# FETbox_rev0_PCB.net
KiCad netlist of a schematic drawn in EAGLE
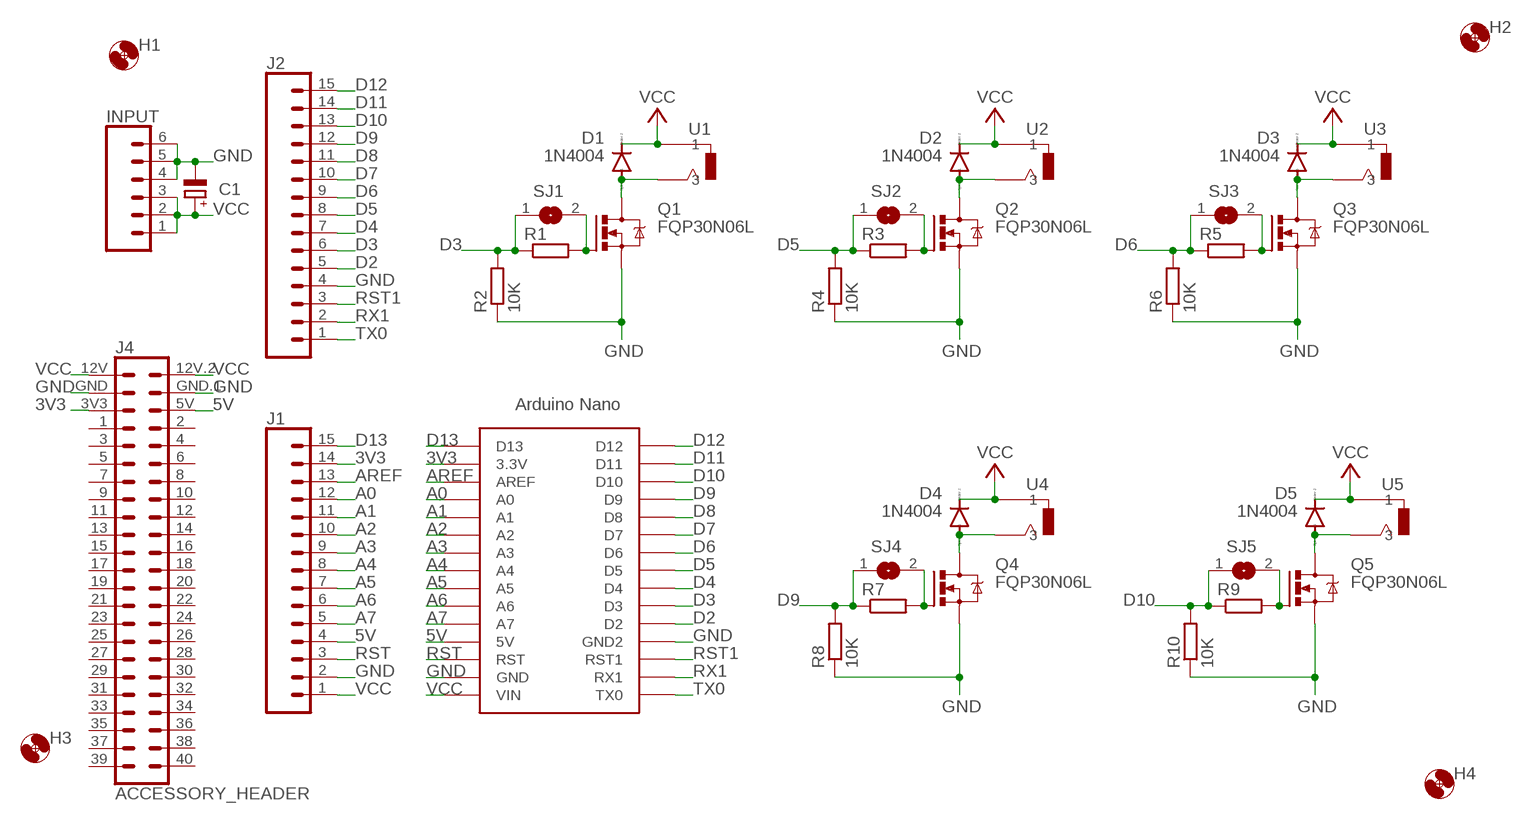
[diagram p0: schematic, sheet 1]

(export (version "E")
  (design (tool "Eeschema 10.0.6"))
  (components
    (comp (ref "C1")
      (value "CPOL-EUE2.5-6")
      (footprint "eagle-import:E2,5-6")
      (libsource (lib "eagle-import") (part "CPOL-EUE2.5-6"))
    )
    (comp (ref "D1")
      (value "1N4004")
      (footprint "eagle-import:DO41-10")
      (libsource (lib "eagle-import") (part "1N4004"))
    )
    (comp (ref "D2")
      (value "1N4004")
      (footprint "eagle-import:DO41-10")
      (libsource (lib "eagle-import") (part "1N4004"))
    )
    (comp (ref "D3")
      (value "1N4004")
      (footprint "eagle-import:DO41-10")
      (libsource (lib "eagle-import") (part "1N4004"))
    )
    (comp (ref "D4")
      (value "1N4004")
      (footprint "eagle-import:DO41-10")
      (libsource (lib "eagle-import") (part "1N4004"))
    )
    (comp (ref "D5")
      (value "1N4004")
      (footprint "eagle-import:DO41-10")
      (libsource (lib "eagle-import") (part "1N4004"))
    )
    (comp (ref "H1")
      (value "MOUNT-HOLE3.0")
      (footprint "eagle-import:3,0")
      (libsource (lib "eagle-import") (part "MOUNT-HOLE3.0"))
    )
    (comp (ref "H2")
      (value "MOUNT-HOLE3.0")
      (footprint "eagle-import:3,0")
      (libsource (lib "eagle-import") (part "MOUNT-HOLE3.0"))
    )
    (comp (ref "H3")
      (value "MOUNT-HOLE3.0")
      (footprint "eagle-import:3,0")
      (libsource (lib "eagle-import") (part "MOUNT-HOLE3.0"))
    )
    (comp (ref "H4")
      (value "MOUNT-HOLE3.0")
      (footprint "eagle-import:3,0")
      (libsource (lib "eagle-import") (part "MOUNT-HOLE3.0"))
    )
    (comp (ref "INPUT")
      (value "CONN_06LONGPADS")
      (footprint "eagle-import:1X06_LONGPADS")
      (libsource (lib "eagle-import") (part "CONN_06LONGPADS"))
    )
    (comp (ref "J1")
      (value "CONN_15")
      (footprint "eagle-import:1X15")
      (libsource (lib "eagle-import") (part "CONN_15"))
    )
    (comp (ref "J2")
      (value "CONN_15")
      (footprint "eagle-import:1X15")
      (libsource (lib "eagle-import") (part "CONN_15"))
    )
    (comp (ref "J4")
      (value "ACCESSORY_HEADER")
      (footprint "eagle-import:2X23")
      (libsource (lib "eagle-import") (part "ACCESSORY_HEADER"))
    )
    (comp (ref "Q1")
      (value "FQP30N06L")
      (footprint "eagle-import:TO220")
      (libsource (lib "eagle-import") (part "FQP30N06L"))
    )
    (comp (ref "Q2")
      (value "FQP30N06L")
      (footprint "eagle-import:TO220")
      (libsource (lib "eagle-import") (part "FQP30N06L"))
    )
    (comp (ref "Q3")
      (value "FQP30N06L")
      (footprint "eagle-import:TO220")
      (libsource (lib "eagle-import") (part "FQP30N06L"))
    )
    (comp (ref "Q4")
      (value "FQP30N06L")
      (footprint "eagle-import:TO220")
      (libsource (lib "eagle-import") (part "FQP30N06L"))
    )
    (comp (ref "Q5")
      (value "FQP30N06L")
      (footprint "eagle-import:TO220")
      (libsource (lib "eagle-import") (part "FQP30N06L"))
    )
    (comp (ref "R1")
      (value "100")
      (footprint "eagle-import:0207_10")
      (libsource (lib "eagle-import") (part "R-EU_0207/10"))
    )
    (comp (ref "R2")
      (value "10K")
      (footprint "eagle-import:0207_10")
      (libsource (lib "eagle-import") (part "R-EU_0207/10"))
    )
    (comp (ref "R3")
      (value "100")
      (footprint "eagle-import:0207_10")
      (libsource (lib "eagle-import") (part "R-EU_0207/10"))
    )
    (comp (ref "R4")
      (value "10K")
      (footprint "eagle-import:0207_10")
      (libsource (lib "eagle-import") (part "R-EU_0207/10"))
    )
    (comp (ref "R5")
      (value "100")
      (footprint "eagle-import:0207_10")
      (libsource (lib "eagle-import") (part "R-EU_0207/10"))
    )
    (comp (ref "R6")
      (value "10K")
      (footprint "eagle-import:0207_10")
      (libsource (lib "eagle-import") (part "R-EU_0207/10"))
    )
    (comp (ref "R7")
      (value "100")
      (footprint "eagle-import:0207_10")
      (libsource (lib "eagle-import") (part "R-EU_0207/10"))
    )
    (comp (ref "R8")
      (value "10K")
      (footprint "eagle-import:0207_10")
      (libsource (lib "eagle-import") (part "R-EU_0207/10"))
    )
    (comp (ref "R9")
      (value "100")
      (footprint "eagle-import:0207_10")
      (libsource (lib "eagle-import") (part "R-EU_0207/10"))
    )
    (comp (ref "R10")
      (value "10K")
      (footprint "eagle-import:0207_10")
      (libsource (lib "eagle-import") (part "R-EU_0207/10"))
    )
    (comp (ref "SJ1") (value "SJ") (footprint "eagle-import:SJ") (libsource (lib "eagle-import") (part "SJ")))
    (comp (ref "SJ2") (value "SJ") (footprint "eagle-import:SJ") (libsource (lib "eagle-import") (part "SJ")))
    (comp (ref "SJ3") (value "SJ") (footprint "eagle-import:SJ") (libsource (lib "eagle-import") (part "SJ")))
    (comp (ref "SJ4") (value "SJ") (footprint "eagle-import:SJ") (libsource (lib "eagle-import") (part "SJ")))
    (comp (ref "SJ5") (value "SJ") (footprint "eagle-import:SJ") (libsource (lib "eagle-import") (part "SJ")))
    (comp (ref "U$2")
      (value "NANO")
      (footprint "eagle-import:NANO")
      (libsource (lib "eagle-import") (part "NANO"))
    )
    (comp (ref "U1")
      (value "CL13845G")
      (footprint "eagle-import:CL13845G")
      (libsource (lib "eagle-import") (part "CL13845G"))
    )
    (comp (ref "U2")
      (value "CL13845G")
      (footprint "eagle-import:CL13845G")
      (libsource (lib "eagle-import") (part "CL13845G"))
    )
    (comp (ref "U3")
      (value "CL13845G")
      (footprint "eagle-import:CL13845G")
      (libsource (lib "eagle-import") (part "CL13845G"))
    )
    (comp (ref "U4")
      (value "CL13845G")
      (footprint "eagle-import:CL13845G")
      (libsource (lib "eagle-import") (part "CL13845G"))
    )
    (comp (ref "U5")
      (value "CL13845G")
      (footprint "eagle-import:CL13845G")
      (libsource (lib "eagle-import") (part "CL13845G"))
    )
  )
  (nets
    (net (code "1") (name "/3V3") (class "Default")
      (node (ref "J1") (pin "14") (pinfunction "14_14") (pintype "passive"))
      (node (ref "J4") (pin "3V3") (pinfunction "3V3_3V3") (pintype "passive"))
      (node (ref "U$2") (pin "3.3V") (pinfunction "3.3V_3.3V") (pintype "bidirectional"))
    )
    (net (code "2") (name "/5V") (class "Default")
      (node (ref "J1") (pin "4") (pinfunction "4_4") (pintype "passive"))
      (node (ref "J4") (pin "5V") (pinfunction "5V_5V") (pintype "passive"))
      (node (ref "U$2") (pin "5V") (pinfunction "5V_5V") (pintype "bidirectional"))
    )
    (net (code "3") (name "/A0") (class "Default")
      (node (ref "J1") (pin "12") (pinfunction "12_12") (pintype "passive"))
      (node (ref "U$2") (pin "A0") (pinfunction "A0_A0") (pintype "bidirectional"))
    )
    (net (code "4") (name "/A1") (class "Default")
      (node (ref "J1") (pin "11") (pinfunction "11_11") (pintype "passive"))
      (node (ref "U$2") (pin "A1") (pinfunction "A1_A1") (pintype "bidirectional"))
    )
    (net (code "5") (name "/A2") (class "Default")
      (node (ref "J1") (pin "10") (pinfunction "10_10") (pintype "passive"))
      (node (ref "U$2") (pin "A2") (pinfunction "A2_A2") (pintype "bidirectional"))
    )
    (net (code "6") (name "/A3") (class "Default")
      (node (ref "J1") (pin "9") (pinfunction "9_9") (pintype "passive"))
      (node (ref "U$2") (pin "A3") (pinfunction "A3_A3") (pintype "bidirectional"))
    )
    (net (code "7") (name "/A4") (class "Default")
      (node (ref "J1") (pin "8") (pinfunction "8_8") (pintype "passive"))
      (node (ref "U$2") (pin "A4") (pinfunction "A4_A4") (pintype "bidirectional"))
    )
    (net (code "8") (name "/A5") (class "Default")
      (node (ref "J1") (pin "7") (pinfunction "7_7") (pintype "passive"))
      (node (ref "U$2") (pin "A5") (pinfunction "A5_A5") (pintype "bidirectional"))
    )
    (net (code "9") (name "/A6") (class "Default")
      (node (ref "J1") (pin "6") (pinfunction "6_6") (pintype "passive"))
      (node (ref "U$2") (pin "A6") (pinfunction "A6_A6") (pintype "bidirectional"))
    )
    (net (code "10") (name "/A7") (class "Default")
      (node (ref "J1") (pin "5") (pinfunction "5_5") (pintype "passive"))
      (node (ref "U$2") (pin "A7") (pinfunction "A7_A7") (pintype "bidirectional"))
    )
    (net (code "11") (name "/AREF") (class "Default")
      (node (ref "J1") (pin "13") (pinfunction "13_13") (pintype "passive"))
      (node (ref "U$2") (pin "AREF") (pinfunction "AREF_AREF") (pintype "bidirectional"))
    )
    (net (code "12") (name "/D2") (class "Default")
      (node (ref "J2") (pin "5") (pinfunction "5_5") (pintype "passive"))
      (node (ref "U$2") (pin "D2") (pinfunction "D2_D2") (pintype "bidirectional"))
    )
    (net (code "13") (name "/D3") (class "Default")
      (node (ref "J2") (pin "6") (pinfunction "6_6") (pintype "passive"))
      (node (ref "R1") (pin "1") (pinfunction "1_1") (pintype "passive"))
      (node (ref "R2") (pin "2") (pinfunction "2_2") (pintype "passive"))
      (node (ref "SJ1") (pin "1") (pinfunction "1_1") (pintype "passive"))
      (node (ref "U$2") (pin "D3") (pinfunction "D3_D3") (pintype "bidirectional"))
    )
    (net (code "14") (name "/D4") (class "Default")
      (node (ref "J2") (pin "7") (pinfunction "7_7") (pintype "passive"))
      (node (ref "U$2") (pin "D4") (pinfunction "D4_D4") (pintype "bidirectional"))
    )
    (net (code "15") (name "/D5") (class "Default")
      (node (ref "J2") (pin "8") (pinfunction "8_8") (pintype "passive"))
      (node (ref "R3") (pin "1") (pinfunction "1_1") (pintype "passive"))
      (node (ref "R4") (pin "2") (pinfunction "2_2") (pintype "passive"))
      (node (ref "SJ2") (pin "1") (pinfunction "1_1") (pintype "passive"))
      (node (ref "U$2") (pin "D5") (pinfunction "D5_D5") (pintype "bidirectional"))
    )
    (net (code "16") (name "/D6") (class "Default")
      (node (ref "J2") (pin "9") (pinfunction "9_9") (pintype "passive"))
      (node (ref "R5") (pin "1") (pinfunction "1_1") (pintype "passive"))
      (node (ref "R6") (pin "2") (pinfunction "2_2") (pintype "passive"))
      (node (ref "SJ3") (pin "1") (pinfunction "1_1") (pintype "passive"))
      (node (ref "U$2") (pin "D6") (pinfunction "D6_D6") (pintype "bidirectional"))
    )
    (net (code "17") (name "/D7") (class "Default")
      (node (ref "J2") (pin "10") (pinfunction "10_10") (pintype "passive"))
      (node (ref "U$2") (pin "D7") (pinfunction "D7_D7") (pintype "bidirectional"))
    )
    (net (code "18") (name "/D8") (class "Default")
      (node (ref "J2") (pin "11") (pinfunction "11_11") (pintype "passive"))
      (node (ref "U$2") (pin "D8") (pinfunction "D8_D8") (pintype "bidirectional"))
    )
    (net (code "19") (name "/D9") (class "Default")
      (node (ref "J2") (pin "12") (pinfunction "12_12") (pintype "passive"))
      (node (ref "R7") (pin "1") (pinfunction "1_1") (pintype "passive"))
      (node (ref "R8") (pin "2") (pinfunction "2_2") (pintype "passive"))
      (node (ref "SJ4") (pin "1") (pinfunction "1_1") (pintype "passive"))
      (node (ref "U$2") (pin "D9") (pinfunction "D9_D9") (pintype "bidirectional"))
    )
    (net (code "20") (name "/D10") (class "Default")
      (node (ref "J2") (pin "13") (pinfunction "13_13") (pintype "passive"))
      (node (ref "R10") (pin "2") (pinfunction "2_2") (pintype "passive"))
      (node (ref "R9") (pin "1") (pinfunction "1_1") (pintype "passive"))
      (node (ref "SJ5") (pin "1") (pinfunction "1_1") (pintype "passive"))
      (node (ref "U$2") (pin "D10") (pinfunction "D10_D10") (pintype "bidirectional"))
    )
    (net (code "21") (name "/D11") (class "Default")
      (node (ref "J2") (pin "14") (pinfunction "14_14") (pintype "passive"))
      (node (ref "U$2") (pin "D11") (pinfunction "D11_D11") (pintype "bidirectional"))
    )
    (net (code "22") (name "/D12") (class "Default")
      (node (ref "J2") (pin "15") (pinfunction "15_15") (pintype "passive"))
      (node (ref "U$2") (pin "D12") (pinfunction "D12_D12") (pintype "bidirectional"))
    )
    (net (code "23") (name "/D13") (class "Default")
      (node (ref "J1") (pin "15") (pinfunction "15_15") (pintype "passive"))
      (node (ref "U$2") (pin "D13") (pinfunction "D13_D13") (pintype "bidirectional"))
    )
    (net (code "24") (name "/GND") (class "Default")
      (node (ref "C1") (pin "-") (pinfunction "-_-") (pintype "passive"))
      (node (ref "INPUT") (pin "4") (pinfunction "4_4") (pintype "passive"))
      (node (ref "INPUT") (pin "5") (pinfunction "5_5") (pintype "passive"))
      (node (ref "INPUT") (pin "6") (pinfunction "6_6") (pintype "passive"))
      (node (ref "J1") (pin "2") (pinfunction "2_2") (pintype "passive"))
      (node (ref "J2") (pin "4") (pinfunction "4_4") (pintype "passive"))
      (node (ref "J4") (pin "GND") (pinfunction "GND_GND") (pintype "passive"))
      (node (ref "J4") (pin "GND.1") (pinfunction "GND.1_GND.1") (pintype "passive"))
      (node (ref "Q1") (pin "S") (pinfunction "S_S") (pintype "passive"))
      (node (ref "Q2") (pin "S") (pinfunction "S_S") (pintype "passive"))
      (node (ref "Q3") (pin "S") (pinfunction "S_S") (pintype "passive"))
      (node (ref "Q4") (pin "S") (pinfunction "S_S") (pintype "passive"))
      (node (ref "Q5") (pin "S") (pinfunction "S_S") (pintype "passive"))
      (node (ref "R10") (pin "1") (pinfunction "1_1") (pintype "passive"))
      (node (ref "R2") (pin "1") (pinfunction "1_1") (pintype "passive"))
      (node (ref "R4") (pin "1") (pinfunction "1_1") (pintype "passive"))
      (node (ref "R6") (pin "1") (pinfunction "1_1") (pintype "passive"))
      (node (ref "R8") (pin "1") (pinfunction "1_1") (pintype "passive"))
      (node (ref "U$2") (pin "GND") (pinfunction "GND_GND") (pintype "bidirectional"))
      (node (ref "U$2") (pin "GND1") (pinfunction "GND2_GND1") (pintype "bidirectional"))
    )
    (net (code "25") (name "/RST") (class "Default")
      (node (ref "J1") (pin "3") (pinfunction "3_3") (pintype "passive"))
      (node (ref "U$2") (pin "RST") (pinfunction "RST_RST") (pintype "bidirectional"))
    )
    (net (code "26") (name "/RST1") (class "Default")
      (node (ref "J2") (pin "3") (pinfunction "3_3") (pintype "passive"))
      (node (ref "U$2") (pin "RST1") (pinfunction "RST1_RST1") (pintype "bidirectional"))
    )
    (net (code "27") (name "/RX1") (class "Default")
      (node (ref "J2") (pin "2") (pinfunction "2_2") (pintype "passive"))
      (node (ref "U$2") (pin "RX1") (pinfunction "RX1_RX1") (pintype "bidirectional"))
    )
    (net (code "28") (name "/TX0") (class "Default")
      (node (ref "J2") (pin "1") (pinfunction "1_1") (pintype "passive"))
      (node (ref "U$2") (pin "TX0") (pinfunction "TX0_TX0") (pintype "bidirectional"))
    )
    (net (code "29") (name "Net-(D1-PadA)") (class "Default")
      (node (ref "D1") (pin "A") (pinfunction "A_A") (pintype "passive"))
      (node (ref "Q1") (pin "D") (pinfunction "D_D") (pintype "passive"))
      (node (ref "U1") (pin "S1") (pinfunction "3_S1") (pintype "passive"))
      (node (ref "U1") (pin "S2") (pinfunction "3_S2") (pintype "passive"))
    )
    (net (code "30") (name "Net-(D2-PadA)") (class "Default")
      (node (ref "D2") (pin "A") (pinfunction "A_A") (pintype "passive"))
      (node (ref "Q2") (pin "D") (pinfunction "D_D") (pintype "passive"))
      (node (ref "U2") (pin "S1") (pinfunction "3_S1") (pintype "passive"))
      (node (ref "U2") (pin "S2") (pinfunction "3_S2") (pintype "passive"))
    )
    (net (code "31") (name "Net-(D3-PadA)") (class "Default")
      (node (ref "D3") (pin "A") (pinfunction "A_A") (pintype "passive"))
      (node (ref "Q3") (pin "D") (pinfunction "D_D") (pintype "passive"))
      (node (ref "U3") (pin "S1") (pinfunction "3_S1") (pintype "passive"))
      (node (ref "U3") (pin "S2") (pinfunction "3_S2") (pintype "passive"))
    )
    (net (code "32") (name "Net-(D4-PadA)") (class "Default")
      (node (ref "D4") (pin "A") (pinfunction "A_A") (pintype "passive"))
      (node (ref "Q4") (pin "D") (pinfunction "D_D") (pintype "passive"))
      (node (ref "U4") (pin "S1") (pinfunction "3_S1") (pintype "passive"))
      (node (ref "U4") (pin "S2") (pinfunction "3_S2") (pintype "passive"))
    )
    (net (code "33") (name "Net-(D5-PadA)") (class "Default")
      (node (ref "D5") (pin "A") (pinfunction "A_A") (pintype "passive"))
      (node (ref "Q5") (pin "D") (pinfunction "D_D") (pintype "passive"))
      (node (ref "U5") (pin "S1") (pinfunction "3_S1") (pintype "passive"))
      (node (ref "U5") (pin "S2") (pinfunction "3_S2") (pintype "passive"))
    )
    (net (code "34") (name "Net-(Q1-PadG)") (class "Default")
      (node (ref "Q1") (pin "G") (pinfunction "G_G") (pintype "passive"))
      (node (ref "R1") (pin "2") (pinfunction "2_2") (pintype "passive"))
      (node (ref "SJ1") (pin "2") (pinfunction "2_2") (pintype "passive"))
    )
    (net (code "35") (name "Net-(Q2-PadG)") (class "Default")
      (node (ref "Q2") (pin "G") (pinfunction "G_G") (pintype "passive"))
      (node (ref "R3") (pin "2") (pinfunction "2_2") (pintype "passive"))
      (node (ref "SJ2") (pin "2") (pinfunction "2_2") (pintype "passive"))
    )
    (net (code "36") (name "Net-(Q3-PadG)") (class "Default")
      (node (ref "Q3") (pin "G") (pinfunction "G_G") (pintype "passive"))
      (node (ref "R5") (pin "2") (pinfunction "2_2") (pintype "passive"))
      (node (ref "SJ3") (pin "2") (pinfunction "2_2") (pintype "passive"))
    )
    (net (code "37") (name "Net-(Q4-PadG)") (class "Default")
      (node (ref "Q4") (pin "G") (pinfunction "G_G") (pintype "passive"))
      (node (ref "R7") (pin "2") (pinfunction "2_2") (pintype "passive"))
      (node (ref "SJ4") (pin "2") (pinfunction "2_2") (pintype "passive"))
    )
    (net (code "38") (name "Net-(Q5-PadG)") (class "Default")
      (node (ref "Q5") (pin "G") (pinfunction "G_G") (pintype "passive"))
      (node (ref "R9") (pin "2") (pinfunction "2_2") (pintype "passive"))
      (node (ref "SJ5") (pin "2") (pinfunction "2_2") (pintype "passive"))
    )
    (net (code "39") (name "VCC") (class "Default")
      (node (ref "C1") (pin "+") (pinfunction "+_+") (pintype "passive"))
      (node (ref "D1") (pin "C") (pinfunction "C_C") (pintype "passive"))
      (node (ref "D2") (pin "C") (pinfunction "C_C") (pintype "passive"))
      (node (ref "D3") (pin "C") (pinfunction "C_C") (pintype "passive"))
      (node (ref "D4") (pin "C") (pinfunction "C_C") (pintype "passive"))
      (node (ref "D5") (pin "C") (pinfunction "C_C") (pintype "passive"))
      (node (ref "INPUT") (pin "1") (pinfunction "1_1") (pintype "passive"))
      (node (ref "INPUT") (pin "2") (pinfunction "2_2") (pintype "passive"))
      (node (ref "INPUT") (pin "3") (pinfunction "3_3") (pintype "passive"))
      (node (ref "J1") (pin "1") (pinfunction "1_1") (pintype "passive"))
      (node (ref "J4") (pin "12V") (pinfunction "12V_12V") (pintype "passive"))
      (node (ref "J4") (pin "12V.2") (pinfunction "12V.1_12V.2") (pintype "passive"))
      (node (ref "U$2") (pin "RAW") (pinfunction "VIN_RAW") (pintype "bidirectional"))
      (node (ref "U1") (pin "T1") (pinfunction "1_T1") (pintype "passive"))
      (node (ref "U1") (pin "T2") (pinfunction "1_T2") (pintype "passive"))
      (node (ref "U2") (pin "T1") (pinfunction "1_T1") (pintype "passive"))
      (node (ref "U2") (pin "T2") (pinfunction "1_T2") (pintype "passive"))
      (node (ref "U3") (pin "T1") (pinfunction "1_T1") (pintype "passive"))
      (node (ref "U3") (pin "T2") (pinfunction "1_T2") (pintype "passive"))
      (node (ref "U4") (pin "T1") (pinfunction "1_T1") (pintype "passive"))
      (node (ref "U4") (pin "T2") (pinfunction "1_T2") (pintype "passive"))
      (node (ref "U5") (pin "T1") (pinfunction "1_T1") (pintype "passive"))
      (node (ref "U5") (pin "T2") (pinfunction "1_T2") (pintype "passive"))
    )
    (net (code "40") (name "unconnected-(J4-Pad1)") (class "Default")
      (node (ref "J4") (pin "1") (pinfunction "1_1") (pintype "passive"))
    )
    (net (code "41") (name "unconnected-(J4-Pad2)") (class "Default")
      (node (ref "J4") (pin "2") (pinfunction "2_2") (pintype "passive"))
    )
    (net (code "42") (name "unconnected-(J4-Pad3)") (class "Default")
      (node (ref "J4") (pin "3") (pinfunction "3_3") (pintype "passive"))
    )
    (net (code "43") (name "unconnected-(J4-Pad4)") (class "Default")
      (node (ref "J4") (pin "4") (pinfunction "4_4") (pintype "passive"))
    )
    (net (code "44") (name "unconnected-(J4-Pad5)") (class "Default")
      (node (ref "J4") (pin "5") (pinfunction "5_5") (pintype "passive"))
    )
    (net (code "45") (name "unconnected-(J4-Pad6)") (class "Default")
      (node (ref "J4") (pin "6") (pinfunction "6_6") (pintype "passive"))
    )
    (net (code "46") (name "unconnected-(J4-Pad7)") (class "Default")
      (node (ref "J4") (pin "7") (pinfunction "7_7") (pintype "passive"))
    )
    (net (code "47") (name "unconnected-(J4-Pad8)") (class "Default")
      (node (ref "J4") (pin "8") (pinfunction "8_8") (pintype "passive"))
    )
    (net (code "48") (name "unconnected-(J4-Pad9)") (class "Default")
      (node (ref "J4") (pin "9") (pinfunction "9_9") (pintype "passive"))
    )
    (net (code "49") (name "unconnected-(J4-Pad10)") (class "Default")
      (node (ref "J4") (pin "10") (pinfunction "10_10") (pintype "passive"))
    )
    (net (code "50") (name "unconnected-(J4-Pad11)") (class "Default")
      (node (ref "J4") (pin "11") (pinfunction "11_11") (pintype "passive"))
    )
    (net (code "51") (name "unconnected-(J4-Pad12)") (class "Default")
      (node (ref "J4") (pin "12") (pinfunction "12_12") (pintype "passive"))
    )
    (net (code "52") (name "unconnected-(J4-Pad13)") (class "Default")
      (node (ref "J4") (pin "13") (pinfunction "13_13") (pintype "passive"))
    )
    (net (code "53") (name "unconnected-(J4-Pad14)") (class "Default")
      (node (ref "J4") (pin "14") (pinfunction "14_14") (pintype "passive"))
    )
    (net (code "54") (name "unconnected-(J4-Pad15)") (class "Default")
      (node (ref "J4") (pin "15") (pinfunction "15_15") (pintype "passive"))
    )
    (net (code "55") (name "unconnected-(J4-Pad16)") (class "Default")
      (node (ref "J4") (pin "16") (pinfunction "16_16") (pintype "passive"))
    )
    (net (code "56") (name "unconnected-(J4-Pad17)") (class "Default")
      (node (ref "J4") (pin "17") (pinfunction "17_17") (pintype "passive"))
    )
    (net (code "57") (name "unconnected-(J4-Pad18)") (class "Default")
      (node (ref "J4") (pin "18") (pinfunction "18_18") (pintype "passive"))
    )
    (net (code "58") (name "unconnected-(J4-Pad19)") (class "Default")
      (node (ref "J4") (pin "19") (pinfunction "19_19") (pintype "passive"))
    )
    (net (code "59") (name "unconnected-(J4-Pad20)") (class "Default")
      (node (ref "J4") (pin "20") (pinfunction "20_20") (pintype "passive"))
    )
    (net (code "60") (name "unconnected-(J4-Pad21)") (class "Default")
      (node (ref "J4") (pin "21") (pinfunction "21_21") (pintype "passive"))
    )
    (net (code "61") (name "unconnected-(J4-Pad22)") (class "Default")
      (node (ref "J4") (pin "22") (pinfunction "22_22") (pintype "passive"))
    )
    (net (code "62") (name "unconnected-(J4-Pad23)") (class "Default")
      (node (ref "J4") (pin "23") (pinfunction "23_23") (pintype "passive"))
    )
    (net (code "63") (name "unconnected-(J4-Pad24)") (class "Default")
      (node (ref "J4") (pin "24") (pinfunction "24_24") (pintype "passive"))
    )
    (net (code "64") (name "unconnected-(J4-Pad25)") (class "Default")
      (node (ref "J4") (pin "25") (pinfunction "25_25") (pintype "passive"))
    )
    (net (code "65") (name "unconnected-(J4-Pad26)") (class "Default")
      (node (ref "J4") (pin "26") (pinfunction "26_26") (pintype "passive"))
    )
    (net (code "66") (name "unconnected-(J4-Pad27)") (class "Default")
      (node (ref "J4") (pin "27") (pinfunction "27_27") (pintype "passive"))
    )
    (net (code "67") (name "unconnected-(J4-Pad28)") (class "Default")
      (node (ref "J4") (pin "28") (pinfunction "28_28") (pintype "passive"))
    )
    (net (code "68") (name "unconnected-(J4-Pad29)") (class "Default")
      (node (ref "J4") (pin "29") (pinfunction "29_29") (pintype "passive"))
    )
    (net (code "69") (name "unconnected-(J4-Pad30)") (class "Default")
      (node (ref "J4") (pin "30") (pinfunction "30_30") (pintype "passive"))
    )
    (net (code "70") (name "unconnected-(J4-Pad31)") (class "Default")
      (node (ref "J4") (pin "31") (pinfunction "31_31") (pintype "passive"))
    )
    (net (code "71") (name "unconnected-(J4-Pad32)") (class "Default")
      (node (ref "J4") (pin "32") (pinfunction "32_32") (pintype "passive"))
    )
    (net (code "72") (name "unconnected-(J4-Pad33)") (class "Default")
      (node (ref "J4") (pin "33") (pinfunction "33_33") (pintype "passive"))
    )
    (net (code "73") (name "unconnected-(J4-Pad34)") (class "Default")
      (node (ref "J4") (pin "34") (pinfunction "34_34") (pintype "passive"))
    )
    (net (code "74") (name "unconnected-(J4-Pad35)") (class "Default")
      (node (ref "J4") (pin "35") (pinfunction "35_35") (pintype "passive"))
    )
    (net (code "75") (name "unconnected-(J4-Pad36)") (class "Default")
      (node (ref "J4") (pin "36") (pinfunction "36_36") (pintype "passive"))
    )
    (net (code "76") (name "unconnected-(J4-Pad37)") (class "Default")
      (node (ref "J4") (pin "37") (pinfunction "37_37") (pintype "passive"))
    )
    (net (code "77") (name "unconnected-(J4-Pad38)") (class "Default")
      (node (ref "J4") (pin "38") (pinfunction "38_38") (pintype "passive"))
    )
    (net (code "78") (name "unconnected-(J4-Pad39)") (class "Default")
      (node (ref "J4") (pin "39") (pinfunction "39_39") (pintype "passive"))
    )
    (net (code "79") (name "unconnected-(J4-Pad40)") (class "Default")
      (node (ref "J4") (pin "40") (pinfunction "40_40") (pintype "passive"))
    )
  )
)
